# Printing4.net
KiCad netlist of a schematic drawn in Altium Designer
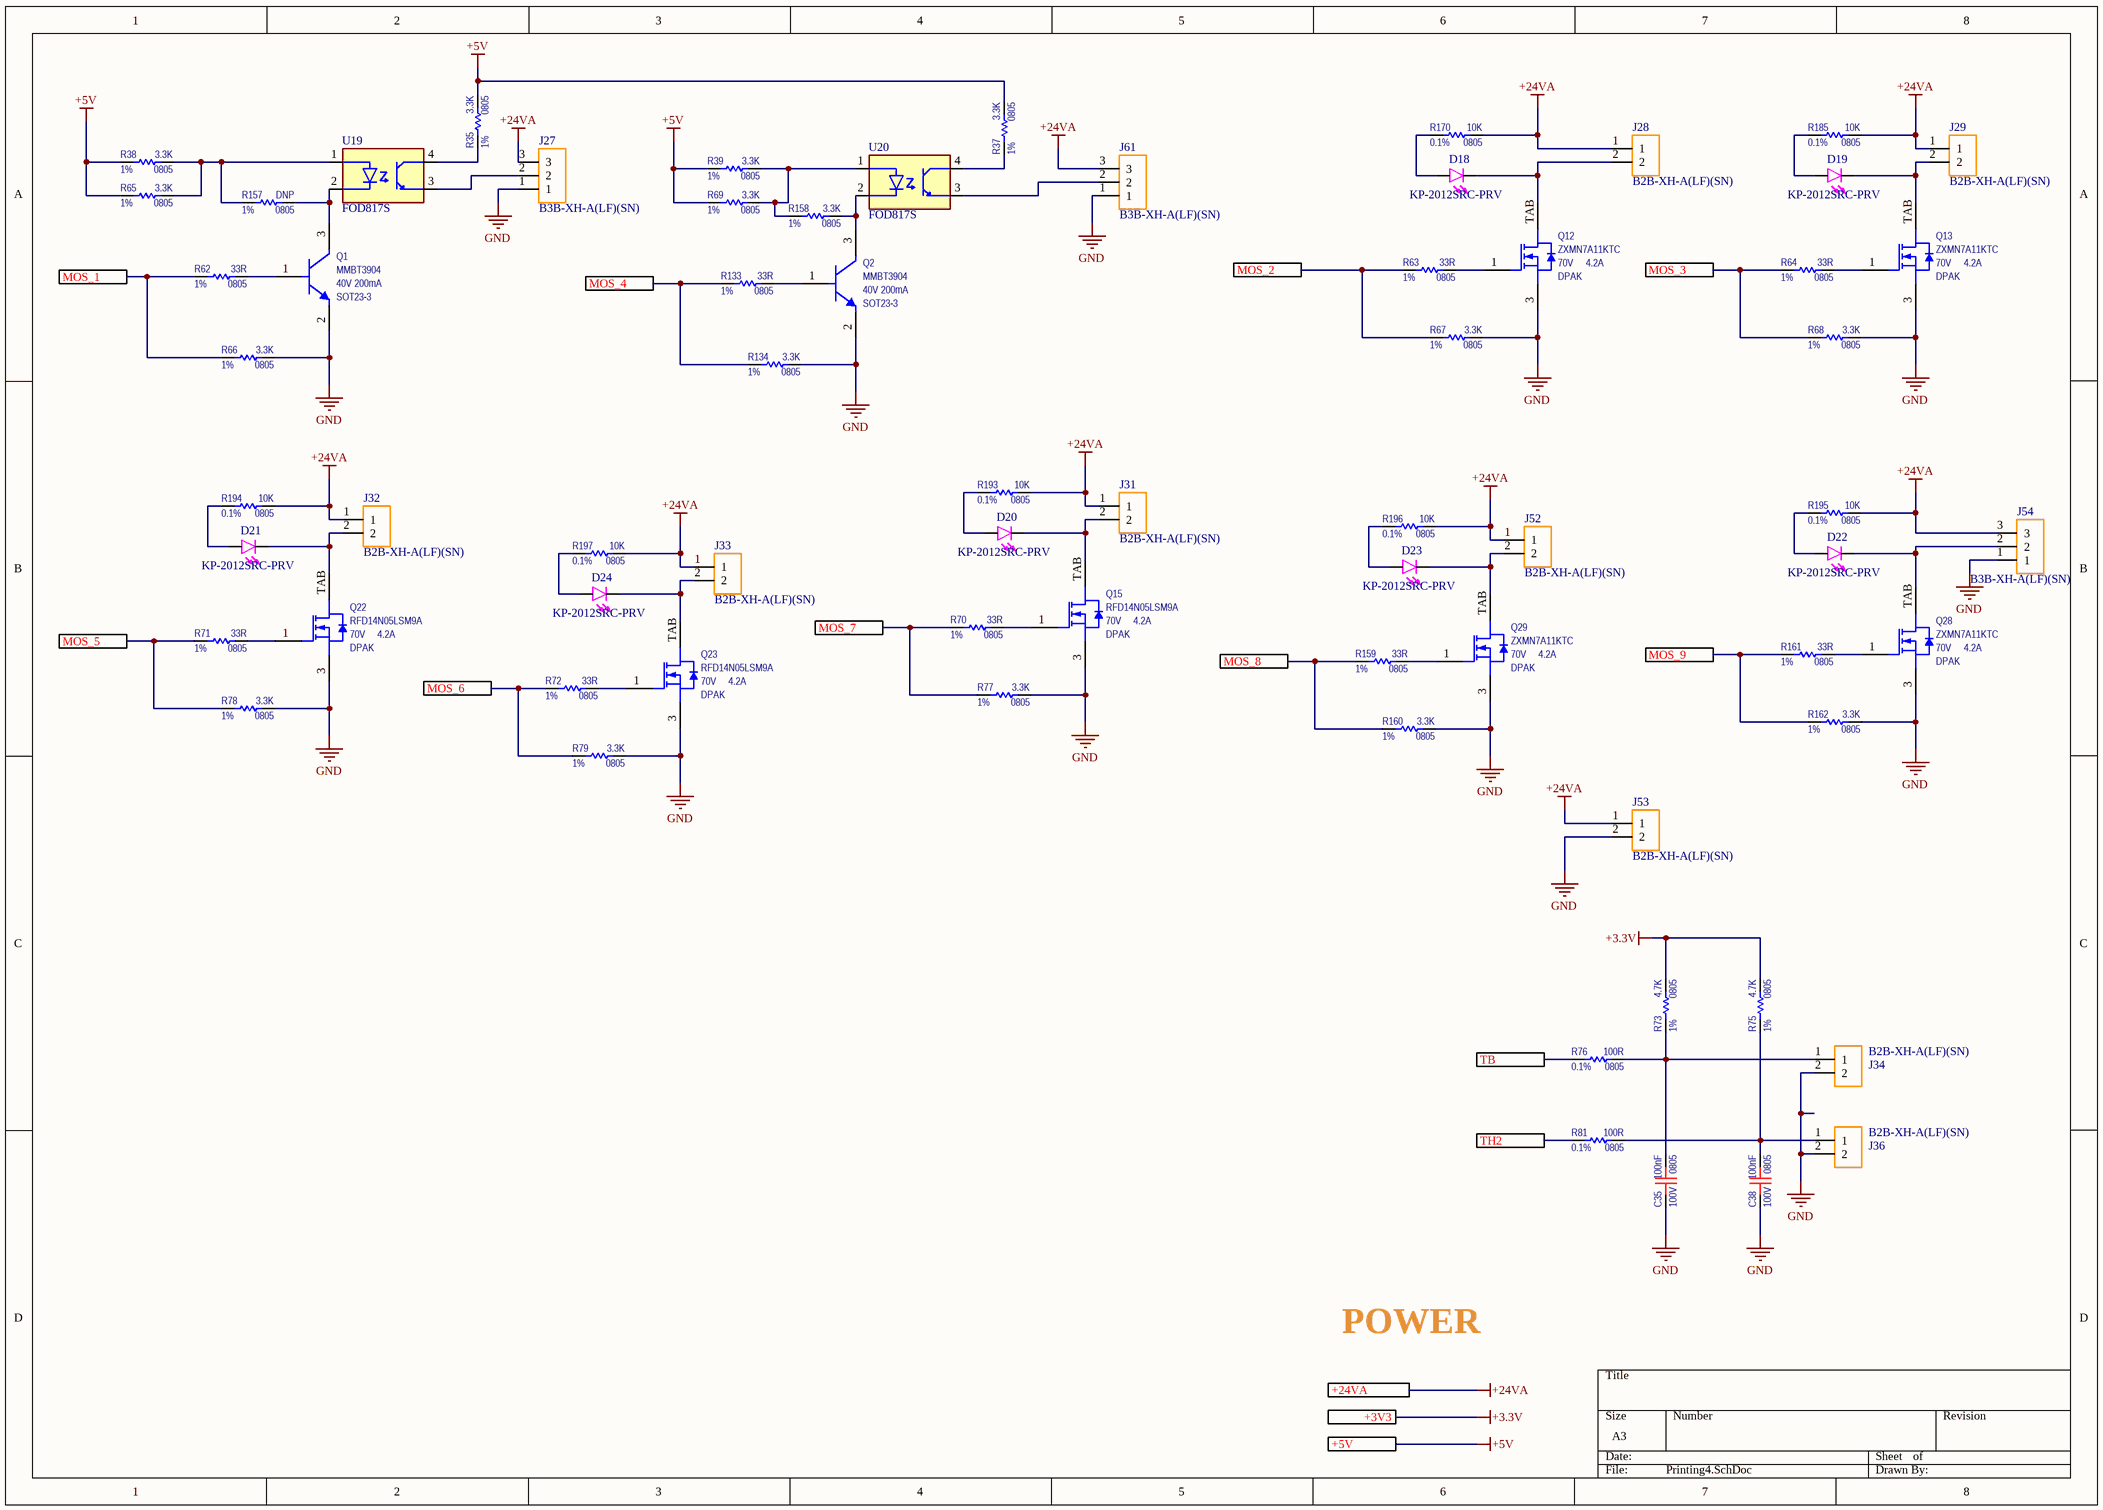
[diagram p0: Printing4.SchDoc]

(export (version "E")
  (design (tool "Eeschema 10.0.6"))
  (components
    (comp (ref "C35")
      (value "100nF")
      (footprint "C_0805_GEN_1.40H")
      (description "CAP_CER_100nF_100V_X7R_10%_0805")
      (fields
        (field (name "VOLTAGE") "100V")
        (field (name "PACKAGE") "0805")
        (field (name "SIMILAR PART") "C0805C104J1RECAUTO7210; C0805X104J1RECAUTO")
        (field (name "TOLERANCE") "10%")
        (field (name "ADDED BY") "İlhanT")
        (field (name "CHECKED BY") "İlkerU")
      )
      (libsource (lib "FireANTs_HwLibDB") (part "ESDSafeCapacitor"))
    )
    (comp (ref "C38")
      (value "100nF")
      (footprint "C_0805_GEN_1.40H")
      (description "CAP_CER_100nF_100V_X7R_10%_0805")
      (fields
        (field (name "VOLTAGE") "100V")
        (field (name "PACKAGE") "0805")
        (field (name "SIMILAR PART") "C0805C104J1RECAUTO7210; C0805X104J1RECAUTO")
        (field (name "TOLERANCE") "10%")
        (field (name "ADDED BY") "İlhanT")
        (field (name "CHECKED BY") "İlkerU")
      )
      (libsource (lib "FireANTs_HwLibDB") (part "ESDSafeCapacitor"))
    )
    (comp (ref "D18")
      (value "KP-2012SRC-PRV")
      (footprint "0805 LED")
      (description "KP-2012SRC-PRV Red LED, 640 nm 2012 (0805), Rectangle Lens SMD package")
      (fields (field (name "MANUFACTURER") "Kingbright"))
      (libsource (lib "Printing") (part "KP-2012SRC-PRV"))
    )
    (comp (ref "D19")
      (value "KP-2012SRC-PRV")
      (footprint "0805 LED")
      (description "KP-2012SRC-PRV Red LED, 640 nm 2012 (0805), Rectangle Lens SMD package")
      (fields (field (name "MANUFACTURER") "Kingbright"))
      (libsource (lib "Printing") (part "KP-2012SRC-PRV"))
    )
    (comp (ref "D20")
      (value "KP-2012SRC-PRV")
      (footprint "0805 LED")
      (description "KP-2012SRC-PRV Red LED, 640 nm 2012 (0805), Rectangle Lens SMD package")
      (fields (field (name "MANUFACTURER") "Kingbright"))
      (libsource (lib "Printing") (part "KP-2012SRC-PRV"))
    )
    (comp (ref "D21")
      (value "KP-2012SRC-PRV")
      (footprint "0805 LED")
      (description "KP-2012SRC-PRV Red LED, 640 nm 2012 (0805), Rectangle Lens SMD package")
      (fields (field (name "MANUFACTURER") "Kingbright"))
      (libsource (lib "Printing") (part "KP-2012SRC-PRV"))
    )
    (comp (ref "D22")
      (value "KP-2012SRC-PRV")
      (footprint "0805 LED")
      (description "KP-2012SRC-PRV Red LED, 640 nm 2012 (0805), Rectangle Lens SMD package")
      (fields (field (name "MANUFACTURER") "Kingbright"))
      (libsource (lib "Printing") (part "KP-2012SRC-PRV"))
    )
    (comp (ref "D23")
      (value "KP-2012SRC-PRV")
      (footprint "0805 LED")
      (description "KP-2012SRC-PRV Red LED, 640 nm 2012 (0805), Rectangle Lens SMD package")
      (fields (field (name "MANUFACTURER") "Kingbright"))
      (libsource (lib "Printing") (part "KP-2012SRC-PRV"))
    )
    (comp (ref "D24")
      (value "KP-2012SRC-PRV")
      (footprint "0805 LED")
      (description "KP-2012SRC-PRV Red LED, 640 nm 2012 (0805), Rectangle Lens SMD package")
      (fields (field (name "MANUFACTURER") "Kingbright"))
      (libsource (lib "Printing") (part "KP-2012SRC-PRV"))
    )
    (comp (ref "J27")
      (value "B3B-XH-A(LF)(SN)")
      (footprint "JST_B3B-XH-A(LF)(SN)")
      (libsource (lib "Printing") (part "B3B-XH-A(LF)(SN)"))
    )
    (comp (ref "J28")
      (value "B2B-XH-A(LF)(SN)")
      (footprint "JST_B2B-XH-A(LF)(SN)")
      (description "Connector Header Through Hole 2 position 0.098 (2.50mm)")
      (fields (field (name "MF") "JST Sales"))
      (libsource (lib "Printing") (part "B2B-XH-A(LF)(SN)"))
    )
    (comp (ref "J29")
      (value "B2B-XH-A(LF)(SN)")
      (footprint "JST_B2B-XH-A(LF)(SN)")
      (description "Connector Header Through Hole 2 position 0.098 (2.50mm)")
      (fields (field (name "MF") "JST Sales"))
      (libsource (lib "Printing") (part "B2B-XH-A(LF)(SN)"))
    )
    (comp (ref "J31")
      (value "B2B-XH-A(LF)(SN)")
      (footprint "JST_B2B-XH-A(LF)(SN)")
      (description "Connector Header Through Hole 2 position 0.098 (2.50mm)")
      (fields (field (name "MF") "JST Sales"))
      (libsource (lib "Printing") (part "B2B-XH-A(LF)(SN)"))
    )
    (comp (ref "J32")
      (value "B2B-XH-A(LF)(SN)")
      (footprint "JST_B2B-XH-A(LF)(SN)")
      (description "Connector Header Through Hole 2 position 0.098 (2.50mm)")
      (fields (field (name "MF") "JST Sales"))
      (libsource (lib "Printing") (part "B2B-XH-A(LF)(SN)"))
    )
    (comp (ref "J33")
      (value "B2B-XH-A(LF)(SN)")
      (footprint "JST_B2B-XH-A(LF)(SN)")
      (description "Connector Header Through Hole 2 position 0.098 (2.50mm)")
      (fields (field (name "MF") "JST Sales"))
      (libsource (lib "Printing") (part "B2B-XH-A(LF)(SN)"))
    )
    (comp (ref "J34")
      (value "B2B-XH-A(LF)(SN)")
      (footprint "JST_B2B-XH-A(LF)(SN)")
      (description "Connector Header Through Hole 2 position 0.098 (2.50mm)")
      (fields (field (name "MF") "JST Sales"))
      (libsource (lib "Printing") (part "B2B-XH-A(LF)(SN)"))
    )
    (comp (ref "J36")
      (value "B2B-XH-A(LF)(SN)")
      (footprint "JST_B2B-XH-A(LF)(SN)")
      (description "Connector Header Through Hole 2 position 0.098 (2.50mm)")
      (fields (field (name "MF") "JST Sales"))
      (libsource (lib "Printing") (part "B2B-XH-A(LF)(SN)"))
    )
    (comp (ref "J52")
      (value "B2B-XH-A(LF)(SN)")
      (footprint "JST_B2B-XH-A(LF)(SN)")
      (description "Connector Header Through Hole 2 position 0.098 (2.50mm)")
      (fields (field (name "MF") "JST Sales"))
      (libsource (lib "Printing") (part "B2B-XH-A(LF)(SN)"))
    )
    (comp (ref "J53")
      (value "B2B-XH-A(LF)(SN)")
      (footprint "JST_B2B-XH-A(LF)(SN)")
      (description "Connector Header Through Hole 2 position 0.098 (2.50mm)")
      (fields (field (name "MF") "JST Sales"))
      (libsource (lib "Printing") (part "B2B-XH-A(LF)(SN)"))
    )
    (comp (ref "J54")
      (value "B3B-XH-A(LF)(SN)")
      (footprint "JST_B3B-XH-A(LF)(SN)")
      (libsource (lib "Printing") (part "B3B-XH-A(LF)(SN)"))
    )
    (comp (ref "J61")
      (value "B3B-XH-A(LF)(SN)")
      (footprint "JST_B3B-XH-A(LF)(SN)")
      (libsource (lib "Printing") (part "B3B-XH-A(LF)(SN)"))
    )
    (comp (ref "Q1")
      (value "MMBT3904")
      (footprint "SOT23-3_MMBT3904,215")
      (description "TRA_NPN_SING_40V_200mA_VSAT300mV_SOT23-3")
      (fields
        (field (name "CURRENT") "200mA")
        (field (name "VOLTAGE") "40V")
        (field (name "PACKAGE") "SOT23-3")
        (field (name "SIMILAR PART") "SST3904HZGT116; PMBT3904,235")
        (field (name "TOLERANCE") "X")
        (field (name "ADDED BY") "HasanA")
        (field (name "CHECKED BY") "EserC")
      )
      (libsource (lib "FireANTs_HwLibDB") (part "SingleNPN_B1E2C3"))
    )
    (comp (ref "Q2")
      (value "MMBT3904")
      (footprint "SOT23-3_MMBT3904,215")
      (description "TRA_NPN_SING_40V_200mA_VSAT300mV_SOT23-3")
      (fields
        (field (name "CURRENT") "200mA")
        (field (name "VOLTAGE") "40V")
        (field (name "PACKAGE") "SOT23-3")
        (field (name "SIMILAR PART") "SST3904HZGT116; PMBT3904,235")
        (field (name "TOLERANCE") "X")
        (field (name "ADDED BY") "HasanA")
        (field (name "CHECKED BY") "EserC")
      )
      (libsource (lib "FireANTs_HwLibDB") (part "SingleNPN_B1E2C3"))
    )
    (comp (ref "Q12")
      (value "ZXMN7A11KTC")
      (footprint "DPAK_SQD50N10-8M9L")
      (description "TRA_NMOS_SING_100V_50A_TH2V_DPAK")
      (fields
        (field (name "CURRENT") "4.2A")
        (field (name "VOLTAGE") "70V")
        (field (name "PACKAGE") "DPAK")
        (field (name "SIMILAR PART") "SQM70060EL_GE3; SQM100N10-10_GE3")
        (field (name "TOLERANCE") "X")
        (field (name "ADDED BY") "İlhanT")
        (field (name "CHECKED BY") "YasinY")
      )
      (libsource (lib "FireANTs_HwLibDB") (part "SingleNMOS_G1S3DTAB"))
    )
    (comp (ref "Q13")
      (value "ZXMN7A11KTC")
      (footprint "DPAK_SQD50N10-8M9L")
      (description "TRA_NMOS_SING_100V_50A_TH2V_DPAK")
      (fields
        (field (name "CURRENT") "4.2A")
        (field (name "VOLTAGE") "70V")
        (field (name "PACKAGE") "DPAK")
        (field (name "SIMILAR PART") "SQM70060EL_GE3; SQM100N10-10_GE3")
        (field (name "TOLERANCE") "X")
        (field (name "ADDED BY") "İlhanT")
        (field (name "CHECKED BY") "YasinY")
      )
      (libsource (lib "FireANTs_HwLibDB") (part "SingleNMOS_G1S3DTAB"))
    )
    (comp (ref "Q15")
      (value "RFD14N05LSM9A")
      (footprint "DPAK_SQD50N10-8M9L")
      (description "TRA_NMOS_SING_100V_50A_TH2V_DPAK")
      (fields
        (field (name "CURRENT") "4.2A")
        (field (name "VOLTAGE") "70V")
        (field (name "PACKAGE") "DPAK")
        (field (name "SIMILAR PART") "SQM70060EL_GE3; SQM100N10-10_GE3")
        (field (name "TOLERANCE") "X")
        (field (name "ADDED BY") "İlhanT")
        (field (name "CHECKED BY") "YasinY")
      )
      (libsource (lib "FireANTs_HwLibDB") (part "SingleNMOS_G1S3DTAB"))
    )
    (comp (ref "Q22")
      (value "RFD14N05LSM9A")
      (footprint "DPAK_SQD50N10-8M9L")
      (description "TRA_NMOS_SING_100V_50A_TH2V_DPAK")
      (fields
        (field (name "CURRENT") "4.2A")
        (field (name "VOLTAGE") "70V")
        (field (name "PACKAGE") "DPAK")
        (field (name "SIMILAR PART") "SQM70060EL_GE3; SQM100N10-10_GE3")
        (field (name "TOLERANCE") "X")
        (field (name "ADDED BY") "İlhanT")
        (field (name "CHECKED BY") "YasinY")
      )
      (libsource (lib "FireANTs_HwLibDB") (part "SingleNMOS_G1S3DTAB"))
    )
    (comp (ref "Q23")
      (value "RFD14N05LSM9A")
      (footprint "DPAK_SQD50N10-8M9L")
      (description "TRA_NMOS_SING_100V_50A_TH2V_DPAK")
      (fields
        (field (name "CURRENT") "4.2A")
        (field (name "VOLTAGE") "70V")
        (field (name "PACKAGE") "DPAK")
        (field (name "SIMILAR PART") "SQM70060EL_GE3; SQM100N10-10_GE3")
        (field (name "TOLERANCE") "X")
        (field (name "ADDED BY") "İlhanT")
        (field (name "CHECKED BY") "YasinY")
      )
      (libsource (lib "FireANTs_HwLibDB") (part "SingleNMOS_G1S3DTAB"))
    )
    (comp (ref "Q28")
      (value "ZXMN7A11KTC")
      (footprint "DPAK_SQD50N10-8M9L")
      (description "TRA_NMOS_SING_100V_50A_TH2V_DPAK")
      (fields
        (field (name "CURRENT") "4.2A")
        (field (name "VOLTAGE") "70V")
        (field (name "PACKAGE") "DPAK")
        (field (name "SIMILAR PART") "SQM70060EL_GE3; SQM100N10-10_GE3")
        (field (name "TOLERANCE") "X")
        (field (name "ADDED BY") "İlhanT")
        (field (name "CHECKED BY") "YasinY")
      )
      (libsource (lib "FireANTs_HwLibDB") (part "SingleNMOS_G1S3DTAB"))
    )
    (comp (ref "Q29")
      (value "ZXMN7A11KTC")
      (footprint "DPAK_SQD50N10-8M9L")
      (description "TRA_NMOS_SING_100V_50A_TH2V_DPAK")
      (fields
        (field (name "CURRENT") "4.2A")
        (field (name "VOLTAGE") "70V")
        (field (name "PACKAGE") "DPAK")
        (field (name "SIMILAR PART") "SQM70060EL_GE3; SQM100N10-10_GE3")
        (field (name "TOLERANCE") "X")
        (field (name "ADDED BY") "İlhanT")
        (field (name "CHECKED BY") "YasinY")
      )
      (libsource (lib "FireANTs_HwLibDB") (part "SingleNMOS_G1S3DTAB"))
    )
    (comp (ref "R35")
      (value "3.3K")
      (footprint "R_0805_GEN_0.70H")
      (description "RES_STD_3.3K_0.125W_1%_100ppm_0805")
      (fields
        (field (name "TOLERANCE") "1%")
        (field (name "PACKAGE") "0805")
        (field (name "VOLTAGE") "150V")
        (field (name "Comment") "StandardResistor")
        (field (name "ADDED BY") "HasanA")
        (field (name "CHECKED BY") "YasinY")
      )
      (libsource (lib "FireANTs_HwLibDB") (part "StandardResistor"))
    )
    (comp (ref "R37")
      (value "3.3K")
      (footprint "R_0805_GEN_0.70H")
      (description "RES_STD_3.3K_0.125W_1%_100ppm_0805")
      (fields
        (field (name "TOLERANCE") "1%")
        (field (name "PACKAGE") "0805")
        (field (name "VOLTAGE") "150V")
        (field (name "Comment") "StandardResistor")
        (field (name "ADDED BY") "HasanA")
        (field (name "CHECKED BY") "YasinY")
      )
      (libsource (lib "FireANTs_HwLibDB") (part "StandardResistor"))
    )
    (comp (ref "R38")
      (value "3.3K")
      (footprint "R_0805_GEN_0.70H")
      (description "RES_STD_3.3K_0.125W_1%_100ppm_0805")
      (fields
        (field (name "TOLERANCE") "1%")
        (field (name "PACKAGE") "0805")
        (field (name "VOLTAGE") "150V")
        (field (name "Comment") "StandardResistor")
        (field (name "ADDED BY") "HasanA")
        (field (name "CHECKED BY") "YasinY")
      )
      (libsource (lib "FireANTs_HwLibDB") (part "StandardResistor"))
    )
    (comp (ref "R39")
      (value "3.3K")
      (footprint "R_0805_GEN_0.70H")
      (description "RES_STD_3.3K_0.125W_1%_100ppm_0805")
      (fields
        (field (name "TOLERANCE") "1%")
        (field (name "PACKAGE") "0805")
        (field (name "VOLTAGE") "150V")
        (field (name "Comment") "StandardResistor")
        (field (name "ADDED BY") "HasanA")
        (field (name "CHECKED BY") "YasinY")
      )
      (libsource (lib "FireANTs_HwLibDB") (part "StandardResistor"))
    )
    (comp (ref "R62")
      (value "33R")
      (footprint "R_0805_GEN_0.70H")
      (description "RES_STD_33R_0.125W_1%_100ppm_0805")
      (fields
        (field (name "TOLERANCE") "1%")
        (field (name "PACKAGE") "0805")
        (field (name "VOLTAGE") "150V")
        (field (name "Comment") "StandardResistor")
        (field (name "ADDED BY") "HasanA")
        (field (name "CHECKED BY") "YasinY")
      )
      (libsource (lib "FireANTs_HwLibDB") (part "StandardResistor"))
    )
    (comp (ref "R63")
      (value "33R")
      (footprint "R_0805_GEN_0.70H")
      (description "RES_STD_33R_0.125W_1%_100ppm_0805")
      (fields
        (field (name "TOLERANCE") "1%")
        (field (name "PACKAGE") "0805")
        (field (name "VOLTAGE") "150V")
        (field (name "Comment") "StandardResistor")
        (field (name "ADDED BY") "HasanA")
        (field (name "CHECKED BY") "YasinY")
      )
      (libsource (lib "FireANTs_HwLibDB") (part "StandardResistor"))
    )
    (comp (ref "R64")
      (value "33R")
      (footprint "R_0805_GEN_0.70H")
      (description "RES_STD_33R_0.125W_1%_100ppm_0805")
      (fields
        (field (name "TOLERANCE") "1%")
        (field (name "PACKAGE") "0805")
        (field (name "VOLTAGE") "150V")
        (field (name "Comment") "StandardResistor")
        (field (name "ADDED BY") "HasanA")
        (field (name "CHECKED BY") "YasinY")
      )
      (libsource (lib "FireANTs_HwLibDB") (part "StandardResistor"))
    )
    (comp (ref "R65")
      (value "3.3K")
      (footprint "R_0805_GEN_0.70H")
      (description "RES_STD_3.3K_0.125W_1%_100ppm_0805")
      (fields
        (field (name "TOLERANCE") "1%")
        (field (name "PACKAGE") "0805")
        (field (name "VOLTAGE") "150V")
        (field (name "Comment") "StandardResistor")
        (field (name "ADDED BY") "HasanA")
        (field (name "CHECKED BY") "YasinY")
      )
      (libsource (lib "FireANTs_HwLibDB") (part "StandardResistor"))
    )
    (comp (ref "R66")
      (value "3.3K")
      (footprint "R_0805_GEN_0.70H")
      (description "RES_STD_3.3K_0.125W_1%_100ppm_0805")
      (fields
        (field (name "TOLERANCE") "1%")
        (field (name "PACKAGE") "0805")
        (field (name "VOLTAGE") "150V")
        (field (name "Comment") "StandardResistor")
        (field (name "ADDED BY") "HasanA")
        (field (name "CHECKED BY") "YasinY")
      )
      (libsource (lib "FireANTs_HwLibDB") (part "StandardResistor"))
    )
    (comp (ref "R67")
      (value "3.3K")
      (footprint "R_0805_GEN_0.70H")
      (description "RES_STD_3.3K_0.125W_1%_100ppm_0805")
      (fields
        (field (name "TOLERANCE") "1%")
        (field (name "PACKAGE") "0805")
        (field (name "VOLTAGE") "150V")
        (field (name "Comment") "StandardResistor")
        (field (name "ADDED BY") "HasanA")
        (field (name "CHECKED BY") "YasinY")
      )
      (libsource (lib "FireANTs_HwLibDB") (part "StandardResistor"))
    )
    (comp (ref "R68")
      (value "3.3K")
      (footprint "R_0805_GEN_0.70H")
      (description "RES_STD_3.3K_0.125W_1%_100ppm_0805")
      (fields
        (field (name "TOLERANCE") "1%")
        (field (name "PACKAGE") "0805")
        (field (name "VOLTAGE") "150V")
        (field (name "Comment") "StandardResistor")
        (field (name "ADDED BY") "HasanA")
        (field (name "CHECKED BY") "YasinY")
      )
      (libsource (lib "FireANTs_HwLibDB") (part "StandardResistor"))
    )
    (comp (ref "R69")
      (value "3.3K")
      (footprint "R_0805_GEN_0.70H")
      (description "RES_STD_3.3K_0.125W_1%_100ppm_0805")
      (fields
        (field (name "TOLERANCE") "1%")
        (field (name "PACKAGE") "0805")
        (field (name "VOLTAGE") "150V")
        (field (name "Comment") "StandardResistor")
        (field (name "ADDED BY") "HasanA")
        (field (name "CHECKED BY") "YasinY")
      )
      (libsource (lib "FireANTs_HwLibDB") (part "StandardResistor"))
    )
    (comp (ref "R70")
      (value "33R")
      (footprint "R_0805_GEN_0.70H")
      (description "RES_STD_33R_0.125W_1%_100ppm_0805")
      (fields
        (field (name "TOLERANCE") "1%")
        (field (name "PACKAGE") "0805")
        (field (name "VOLTAGE") "150V")
        (field (name "Comment") "StandardResistor")
        (field (name "ADDED BY") "HasanA")
        (field (name "CHECKED BY") "YasinY")
      )
      (libsource (lib "FireANTs_HwLibDB") (part "StandardResistor"))
    )
    (comp (ref "R71")
      (value "33R")
      (footprint "R_0805_GEN_0.70H")
      (description "RES_STD_33R_0.125W_1%_100ppm_0805")
      (fields
        (field (name "TOLERANCE") "1%")
        (field (name "PACKAGE") "0805")
        (field (name "VOLTAGE") "150V")
        (field (name "Comment") "StandardResistor")
        (field (name "ADDED BY") "HasanA")
        (field (name "CHECKED BY") "YasinY")
      )
      (libsource (lib "FireANTs_HwLibDB") (part "StandardResistor"))
    )
    (comp (ref "R72")
      (value "33R")
      (footprint "R_0805_GEN_0.70H")
      (description "RES_STD_33R_0.125W_1%_100ppm_0805")
      (fields
        (field (name "TOLERANCE") "1%")
        (field (name "PACKAGE") "0805")
        (field (name "VOLTAGE") "150V")
        (field (name "Comment") "StandardResistor")
        (field (name "ADDED BY") "HasanA")
        (field (name "CHECKED BY") "YasinY")
      )
      (libsource (lib "FireANTs_HwLibDB") (part "StandardResistor"))
    )
    (comp (ref "R73")
      (value "4.7K")
      (footprint "R_0805_GEN_0.60H")
      (description "RES_STD_4.7K_0.125W_1%_100ppm_0805")
      (fields
        (field (name "TOLERANCE") "1%")
        (field (name "PACKAGE") "0805")
        (field (name "VOLTAGE") "150V")
        (field (name "Comment") "StandardResistor")
        (field (name "ADDED BY") "SonerI")
        (field (name "CHECKED BY") "YasinY")
      )
      (libsource (lib "FireANTs_HwLibDB") (part "StandardResistor"))
    )
    (comp (ref "R75")
      (value "4.7K")
      (footprint "R_0805_GEN_0.60H")
      (description "RES_STD_4.7K_0.125W_1%_100ppm_0805")
      (fields
        (field (name "TOLERANCE") "1%")
        (field (name "PACKAGE") "0805")
        (field (name "VOLTAGE") "150V")
        (field (name "Comment") "StandardResistor")
        (field (name "ADDED BY") "SonerI")
        (field (name "CHECKED BY") "YasinY")
      )
      (libsource (lib "FireANTs_HwLibDB") (part "StandardResistor"))
    )
    (comp (ref "R76")
      (value "100R")
      (footprint "R_0805_GEN_0.70H")
      (description "RES_STD_100R_0.125W_0.1%_10ppm_0805")
      (fields
        (field (name "TOLERANCE") "0.1%")
        (field (name "PACKAGE") "0805")
        (field (name "SIMILAR PART") "RNCF0805TKY100R; RG2012N-101-W-T1")
        (field (name "VOLTAGE") "150V")
        (field (name "ADDED BY") "HasanA")
        (field (name "CHECKED BY") "YasinY")
      )
      (libsource (lib "FireANTs_HwLibDB") (part "StandardResistor"))
    )
    (comp (ref "R77")
      (value "3.3K")
      (footprint "R_0805_GEN_0.70H")
      (description "RES_STD_3.3K_0.125W_1%_100ppm_0805")
      (fields
        (field (name "TOLERANCE") "1%")
        (field (name "PACKAGE") "0805")
        (field (name "VOLTAGE") "150V")
        (field (name "Comment") "StandardResistor")
        (field (name "ADDED BY") "HasanA")
        (field (name "CHECKED BY") "YasinY")
      )
      (libsource (lib "FireANTs_HwLibDB") (part "StandardResistor"))
    )
    (comp (ref "R78")
      (value "3.3K")
      (footprint "R_0805_GEN_0.70H")
      (description "RES_STD_3.3K_0.125W_1%_100ppm_0805")
      (fields
        (field (name "TOLERANCE") "1%")
        (field (name "PACKAGE") "0805")
        (field (name "VOLTAGE") "150V")
        (field (name "Comment") "StandardResistor")
        (field (name "ADDED BY") "HasanA")
        (field (name "CHECKED BY") "YasinY")
      )
      (libsource (lib "FireANTs_HwLibDB") (part "StandardResistor"))
    )
    (comp (ref "R79")
      (value "3.3K")
      (footprint "R_0805_GEN_0.70H")
      (description "RES_STD_3.3K_0.125W_1%_100ppm_0805")
      (fields
        (field (name "TOLERANCE") "1%")
        (field (name "PACKAGE") "0805")
        (field (name "VOLTAGE") "150V")
        (field (name "Comment") "StandardResistor")
        (field (name "ADDED BY") "HasanA")
        (field (name "CHECKED BY") "YasinY")
      )
      (libsource (lib "FireANTs_HwLibDB") (part "StandardResistor"))
    )
    (comp (ref "R81")
      (value "100R")
      (footprint "R_0805_GEN_0.70H")
      (description "RES_STD_100R_0.125W_0.1%_10ppm_0805")
      (fields
        (field (name "TOLERANCE") "0.1%")
        (field (name "PACKAGE") "0805")
        (field (name "SIMILAR PART") "RNCF0805TKY100R; RG2012N-101-W-T1")
        (field (name "VOLTAGE") "150V")
        (field (name "ADDED BY") "HasanA")
        (field (name "CHECKED BY") "YasinY")
      )
      (libsource (lib "FireANTs_HwLibDB") (part "StandardResistor"))
    )
    (comp (ref "R133")
      (value "33R")
      (footprint "R_0805_GEN_0.70H")
      (description "RES_STD_33R_0.125W_1%_100ppm_0805")
      (fields
        (field (name "TOLERANCE") "1%")
        (field (name "PACKAGE") "0805")
        (field (name "VOLTAGE") "150V")
        (field (name "Comment") "StandardResistor")
        (field (name "ADDED BY") "HasanA")
        (field (name "CHECKED BY") "YasinY")
      )
      (libsource (lib "FireANTs_HwLibDB") (part "StandardResistor"))
    )
    (comp (ref "R134")
      (value "3.3K")
      (footprint "R_0805_GEN_0.70H")
      (description "RES_STD_3.3K_0.125W_1%_100ppm_0805")
      (fields
        (field (name "TOLERANCE") "1%")
        (field (name "PACKAGE") "0805")
        (field (name "VOLTAGE") "150V")
        (field (name "Comment") "StandardResistor")
        (field (name "ADDED BY") "HasanA")
        (field (name "CHECKED BY") "YasinY")
      )
      (libsource (lib "FireANTs_HwLibDB") (part "StandardResistor"))
    )
    (comp (ref "R157")
      (value "DNP")
      (footprint "R_0805_GEN_0.70H")
      (description "RES_STD_3.3K_0.125W_1%_100ppm_0805")
      (fields
        (field (name "TOLERANCE") "1%")
        (field (name "PACKAGE") "0805")
        (field (name "VOLTAGE") "150V")
        (field (name "Comment") "StandardResistor")
        (field (name "ADDED BY") "HasanA")
        (field (name "CHECKED BY") "YasinY")
      )
      (libsource (lib "FireANTs_HwLibDB") (part "StandardResistor"))
    )
    (comp (ref "R158")
      (value "3.3K")
      (footprint "R_0805_GEN_0.70H")
      (description "RES_STD_3.3K_0.125W_1%_100ppm_0805")
      (fields
        (field (name "TOLERANCE") "1%")
        (field (name "PACKAGE") "0805")
        (field (name "VOLTAGE") "150V")
        (field (name "Comment") "StandardResistor")
        (field (name "ADDED BY") "HasanA")
        (field (name "CHECKED BY") "YasinY")
      )
      (libsource (lib "FireANTs_HwLibDB") (part "StandardResistor"))
    )
    (comp (ref "R159")
      (value "33R")
      (footprint "R_0805_GEN_0.70H")
      (description "RES_STD_33R_0.125W_1%_100ppm_0805")
      (fields
        (field (name "TOLERANCE") "1%")
        (field (name "PACKAGE") "0805")
        (field (name "VOLTAGE") "150V")
        (field (name "Comment") "StandardResistor")
        (field (name "ADDED BY") "HasanA")
        (field (name "CHECKED BY") "YasinY")
      )
      (libsource (lib "FireANTs_HwLibDB") (part "StandardResistor"))
    )
    (comp (ref "R160")
      (value "3.3K")
      (footprint "R_0805_GEN_0.70H")
      (description "RES_STD_3.3K_0.125W_1%_100ppm_0805")
      (fields
        (field (name "TOLERANCE") "1%")
        (field (name "PACKAGE") "0805")
        (field (name "VOLTAGE") "150V")
        (field (name "Comment") "StandardResistor")
        (field (name "ADDED BY") "HasanA")
        (field (name "CHECKED BY") "YasinY")
      )
      (libsource (lib "FireANTs_HwLibDB") (part "StandardResistor"))
    )
    (comp (ref "R161")
      (value "33R")
      (footprint "R_0805_GEN_0.70H")
      (description "RES_STD_33R_0.125W_1%_100ppm_0805")
      (fields
        (field (name "TOLERANCE") "1%")
        (field (name "PACKAGE") "0805")
        (field (name "VOLTAGE") "150V")
        (field (name "Comment") "StandardResistor")
        (field (name "ADDED BY") "HasanA")
        (field (name "CHECKED BY") "YasinY")
      )
      (libsource (lib "FireANTs_HwLibDB") (part "StandardResistor"))
    )
    (comp (ref "R162")
      (value "3.3K")
      (footprint "R_0805_GEN_0.70H")
      (description "RES_STD_3.3K_0.125W_1%_100ppm_0805")
      (fields
        (field (name "TOLERANCE") "1%")
        (field (name "PACKAGE") "0805")
        (field (name "VOLTAGE") "150V")
        (field (name "Comment") "StandardResistor")
        (field (name "ADDED BY") "HasanA")
        (field (name "CHECKED BY") "YasinY")
      )
      (libsource (lib "FireANTs_HwLibDB") (part "StandardResistor"))
    )
    (comp (ref "R170")
      (value "10K")
      (footprint "R_0805_GEN_0.70H")
      (description "RES_STD_2K_0.125W_0.1%_25ppm_0805")
      (fields
        (field (name "TOLERANCE") "0.1%")
        (field (name "PACKAGE") "0805")
        (field (name "SIMILAR PART") "ERA-6ARB202V")
        (field (name "VOLTAGE") "100V")
        (field (name "ADDED BY") "İlhanT")
        (field (name "CHECKED BY") "YasinY")
      )
      (libsource (lib "FireANTs_HwLibDB") (part "StandardResistor"))
    )
    (comp (ref "R185")
      (value "10K")
      (footprint "R_0805_GEN_0.70H")
      (description "RES_STD_2K_0.125W_0.1%_25ppm_0805")
      (fields
        (field (name "TOLERANCE") "0.1%")
        (field (name "PACKAGE") "0805")
        (field (name "SIMILAR PART") "ERA-6ARB202V")
        (field (name "VOLTAGE") "100V")
        (field (name "ADDED BY") "İlhanT")
        (field (name "CHECKED BY") "YasinY")
      )
      (libsource (lib "FireANTs_HwLibDB") (part "StandardResistor"))
    )
    (comp (ref "R193")
      (value "10K")
      (footprint "R_0805_GEN_0.70H")
      (description "RES_STD_2K_0.125W_0.1%_25ppm_0805")
      (fields
        (field (name "TOLERANCE") "0.1%")
        (field (name "PACKAGE") "0805")
        (field (name "SIMILAR PART") "ERA-6ARB202V")
        (field (name "VOLTAGE") "100V")
        (field (name "ADDED BY") "İlhanT")
        (field (name "CHECKED BY") "YasinY")
      )
      (libsource (lib "FireANTs_HwLibDB") (part "StandardResistor"))
    )
    (comp (ref "R194")
      (value "10K")
      (footprint "R_0805_GEN_0.70H")
      (description "RES_STD_2K_0.125W_0.1%_25ppm_0805")
      (fields
        (field (name "TOLERANCE") "0.1%")
        (field (name "PACKAGE") "0805")
        (field (name "SIMILAR PART") "ERA-6ARB202V")
        (field (name "VOLTAGE") "100V")
        (field (name "ADDED BY") "İlhanT")
        (field (name "CHECKED BY") "YasinY")
      )
      (libsource (lib "FireANTs_HwLibDB") (part "StandardResistor"))
    )
    (comp (ref "R195")
      (value "10K")
      (footprint "R_0805_GEN_0.70H")
      (description "RES_STD_2K_0.125W_0.1%_25ppm_0805")
      (fields
        (field (name "TOLERANCE") "0.1%")
        (field (name "PACKAGE") "0805")
        (field (name "SIMILAR PART") "ERA-6ARB202V")
        (field (name "VOLTAGE") "100V")
        (field (name "ADDED BY") "İlhanT")
        (field (name "CHECKED BY") "YasinY")
      )
      (libsource (lib "FireANTs_HwLibDB") (part "StandardResistor"))
    )
    (comp (ref "R196")
      (value "10K")
      (footprint "R_0805_GEN_0.70H")
      (description "RES_STD_2K_0.125W_0.1%_25ppm_0805")
      (fields
        (field (name "TOLERANCE") "0.1%")
        (field (name "PACKAGE") "0805")
        (field (name "SIMILAR PART") "ERA-6ARB202V")
        (field (name "VOLTAGE") "100V")
        (field (name "ADDED BY") "İlhanT")
        (field (name "CHECKED BY") "YasinY")
      )
      (libsource (lib "FireANTs_HwLibDB") (part "StandardResistor"))
    )
    (comp (ref "R197")
      (value "10K")
      (footprint "R_0805_GEN_0.70H")
      (description "RES_STD_2K_0.125W_0.1%_25ppm_0805")
      (fields
        (field (name "TOLERANCE") "0.1%")
        (field (name "PACKAGE") "0805")
        (field (name "SIMILAR PART") "ERA-6ARB202V")
        (field (name "VOLTAGE") "100V")
        (field (name "ADDED BY") "İlhanT")
        (field (name "CHECKED BY") "YasinY")
      )
      (libsource (lib "FireANTs_HwLibDB") (part "StandardResistor"))
    )
    (comp (ref "U19")
      (value "FOD817S")
      (footprint "SOIC254P1016X385-4N")
      (description "Optoisolator Transistor Output 5000Vrms 1 Channel 4-SMD")
      (fields (field (name "MF") "ON Semiconductor"))
      (libsource (lib "Printing") (part "FOD817S"))
    )
    (comp (ref "U20")
      (value "FOD817S")
      (footprint "SOIC254P1016X385-4N")
      (description "Optoisolator Transistor Output 5000Vrms 1 Channel 4-SMD")
      (fields (field (name "MF") "ON Semiconductor"))
      (libsource (lib "Printing") (part "FOD817S"))
    )
  )
  (nets
    (net (code "1") (name "+3.3V") (class "Default")
      (node (ref "R73") (pin "2") (pinfunction "2_2") (pintype "passive"))
      (node (ref "R75") (pin "2") (pinfunction "2_2") (pintype "passive"))
    )
    (net (code "2") (name "+5V") (class "Default")
      (node (ref "R35") (pin "2") (pinfunction "2_2") (pintype "passive"))
      (node (ref "R37") (pin "2") (pinfunction "2_2") (pintype "passive"))
      (node (ref "R38") (pin "1") (pinfunction "1_1") (pintype "passive"))
      (node (ref "R39") (pin "1") (pinfunction "1_1") (pintype "passive"))
      (node (ref "R65") (pin "1") (pinfunction "1_1") (pintype "passive"))
      (node (ref "R69") (pin "1") (pinfunction "1_1") (pintype "passive"))
    )
    (net (code "3") (name "+24VA") (class "Default")
      (node (ref "J27") (pin "3") (pinfunction "3_3") (pintype "passive"))
      (node (ref "J28") (pin "1") (pinfunction "1_1") (pintype "passive"))
      (node (ref "J29") (pin "1") (pinfunction "1_1") (pintype "passive"))
      (node (ref "J31") (pin "1") (pinfunction "1_1") (pintype "passive"))
      (node (ref "J32") (pin "1") (pinfunction "1_1") (pintype "passive"))
      (node (ref "J33") (pin "1") (pinfunction "1_1") (pintype "passive"))
      (node (ref "J52") (pin "1") (pinfunction "1_1") (pintype "passive"))
      (node (ref "J53") (pin "1") (pinfunction "1_1") (pintype "passive"))
      (node (ref "J54") (pin "3") (pinfunction "3_3") (pintype "passive"))
      (node (ref "J61") (pin "3") (pinfunction "3_3") (pintype "passive"))
      (node (ref "R170") (pin "2") (pinfunction "2_2") (pintype "passive"))
      (node (ref "R185") (pin "2") (pinfunction "2_2") (pintype "passive"))
      (node (ref "R193") (pin "2") (pinfunction "2_2") (pintype "passive"))
      (node (ref "R194") (pin "2") (pinfunction "2_2") (pintype "passive"))
      (node (ref "R195") (pin "2") (pinfunction "2_2") (pintype "passive"))
      (node (ref "R196") (pin "2") (pinfunction "2_2") (pintype "passive"))
      (node (ref "R197") (pin "2") (pinfunction "2_2") (pintype "passive"))
    )
    (net (code "4") (name "/MOS_1") (class "Default")
      (node (ref "R62") (pin "1") (pinfunction "1_1") (pintype "passive"))
      (node (ref "R66") (pin "1") (pinfunction "1_1") (pintype "passive"))
    )
    (net (code "5") (name "/MOS_2") (class "Default")
      (node (ref "R63") (pin "1") (pinfunction "1_1") (pintype "passive"))
      (node (ref "R67") (pin "1") (pinfunction "1_1") (pintype "passive"))
    )
    (net (code "6") (name "/MOS_3") (class "Default")
      (node (ref "R64") (pin "1") (pinfunction "1_1") (pintype "passive"))
      (node (ref "R68") (pin "1") (pinfunction "1_1") (pintype "passive"))
    )
    (net (code "7") (name "/MOS_4") (class "Default")
      (node (ref "R133") (pin "1") (pinfunction "1_1") (pintype "passive"))
      (node (ref "R134") (pin "1") (pinfunction "1_1") (pintype "passive"))
    )
    (net (code "8") (name "/MOS_5") (class "Default")
      (node (ref "R71") (pin "1") (pinfunction "1_1") (pintype "passive"))
      (node (ref "R78") (pin "1") (pinfunction "1_1") (pintype "passive"))
    )
    (net (code "9") (name "/MOS_6") (class "Default")
      (node (ref "R72") (pin "1") (pinfunction "1_1") (pintype "passive"))
      (node (ref "R79") (pin "1") (pinfunction "1_1") (pintype "passive"))
    )
    (net (code "10") (name "/MOS_7") (class "Default")
      (node (ref "R70") (pin "1") (pinfunction "1_1") (pintype "passive"))
      (node (ref "R77") (pin "1") (pinfunction "1_1") (pintype "passive"))
    )
    (net (code "11") (name "/MOS_8") (class "Default")
      (node (ref "R159") (pin "1") (pinfunction "1_1") (pintype "passive"))
      (node (ref "R160") (pin "1") (pinfunction "1_1") (pintype "passive"))
    )
    (net (code "12") (name "/MOS_9") (class "Default")
      (node (ref "R161") (pin "1") (pinfunction "1_1") (pintype "passive"))
      (node (ref "R162") (pin "1") (pinfunction "1_1") (pintype "passive"))
    )
    (net (code "13") (name "/TB") (class "Default")
      (node (ref "R76") (pin "1") (pinfunction "1_1") (pintype "passive"))
    )
    (net (code "14") (name "/TH2") (class "Default")
      (node (ref "R81") (pin "1") (pinfunction "1_1") (pintype "passive"))
    )
    (net (code "15") (name "GND") (class "Default")
      (node (ref "C35") (pin "1") (pinfunction "1_1") (pintype "passive"))
      (node (ref "C38") (pin "1") (pinfunction "1_1") (pintype "passive"))
      (node (ref "J27") (pin "1") (pinfunction "1_1") (pintype "passive"))
      (node (ref "J34") (pin "2") (pinfunction "2_2") (pintype "passive"))
      (node (ref "J36") (pin "2") (pinfunction "2_2") (pintype "passive"))
      (node (ref "J53") (pin "2") (pinfunction "2_2") (pintype "passive"))
      (node (ref "J54") (pin "1") (pinfunction "1_1") (pintype "passive"))
      (node (ref "J61") (pin "1") (pinfunction "1_1") (pintype "passive"))
      (node (ref "Q1") (pin "2") (pinfunction "EMITTER_2") (pintype "passive"))
      (node (ref "Q12") (pin "3") (pinfunction "SOURCE_3") (pintype "passive"))
      (node (ref "Q13") (pin "3") (pinfunction "SOURCE_3") (pintype "passive"))
      (node (ref "Q15") (pin "3") (pinfunction "SOURCE_3") (pintype "passive"))
      (node (ref "Q2") (pin "2") (pinfunction "EMITTER_2") (pintype "passive"))
      (node (ref "Q22") (pin "3") (pinfunction "SOURCE_3") (pintype "passive"))
      (node (ref "Q23") (pin "3") (pinfunction "SOURCE_3") (pintype "passive"))
      (node (ref "Q28") (pin "3") (pinfunction "SOURCE_3") (pintype "passive"))
      (node (ref "Q29") (pin "3") (pinfunction "SOURCE_3") (pintype "passive"))
      (node (ref "R134") (pin "2") (pinfunction "2_2") (pintype "passive"))
      (node (ref "R160") (pin "2") (pinfunction "2_2") (pintype "passive"))
      (node (ref "R162") (pin "2") (pinfunction "2_2") (pintype "passive"))
      (node (ref "R66") (pin "2") (pinfunction "2_2") (pintype "passive"))
      (node (ref "R67") (pin "2") (pinfunction "2_2") (pintype "passive"))
      (node (ref "R68") (pin "2") (pinfunction "2_2") (pintype "passive"))
      (node (ref "R77") (pin "2") (pinfunction "2_2") (pintype "passive"))
      (node (ref "R78") (pin "2") (pinfunction "2_2") (pintype "passive"))
      (node (ref "R79") (pin "2") (pinfunction "2_2") (pintype "passive"))
    )
    (net (code "16") (name "Net-(C35-Pad2)") (class "Default")
      (node (ref "C35") (pin "2") (pinfunction "2_2") (pintype "passive"))
      (node (ref "J34") (pin "1") (pinfunction "1_1") (pintype "passive"))
      (node (ref "R73") (pin "1") (pinfunction "1_1") (pintype "passive"))
      (node (ref "R76") (pin "2") (pinfunction "2_2") (pintype "passive"))
    )
    (net (code "17") (name "Net-(C38-Pad2)") (class "Default")
      (node (ref "C38") (pin "2") (pinfunction "2_2") (pintype "passive"))
      (node (ref "J36") (pin "1") (pinfunction "1_1") (pintype "passive"))
      (node (ref "R75") (pin "1") (pinfunction "1_1") (pintype "passive"))
      (node (ref "R81") (pin "2") (pinfunction "2_2") (pintype "passive"))
    )
    (net (code "18") (name "Net-(D18-C)") (class "Default")
      (node (ref "D18") (pin "K") (pinfunction "C_K") (pintype "passive"))
      (node (ref "J28") (pin "2") (pinfunction "2_2") (pintype "passive"))
      (node (ref "Q12") (pin "TAB") (pinfunction "DRAIN_TAB") (pintype "passive"))
    )
    (net (code "19") (name "Net-(D18-PadA)") (class "Default")
      (node (ref "D18") (pin "A") (pinfunction "A_A") (pintype "passive"))
      (node (ref "R170") (pin "1") (pinfunction "1_1") (pintype "passive"))
    )
    (net (code "20") (name "Net-(D19-C)") (class "Default")
      (node (ref "D19") (pin "K") (pinfunction "C_K") (pintype "passive"))
      (node (ref "J29") (pin "2") (pinfunction "2_2") (pintype "passive"))
      (node (ref "Q13") (pin "TAB") (pinfunction "DRAIN_TAB") (pintype "passive"))
    )
    (net (code "21") (name "Net-(D19-PadA)") (class "Default")
      (node (ref "D19") (pin "A") (pinfunction "A_A") (pintype "passive"))
      (node (ref "R185") (pin "1") (pinfunction "1_1") (pintype "passive"))
    )
    (net (code "22") (name "Net-(D20-C)") (class "Default")
      (node (ref "D20") (pin "K") (pinfunction "C_K") (pintype "passive"))
      (node (ref "J31") (pin "2") (pinfunction "2_2") (pintype "passive"))
      (node (ref "Q15") (pin "TAB") (pinfunction "DRAIN_TAB") (pintype "passive"))
    )
    (net (code "23") (name "Net-(D20-PadA)") (class "Default")
      (node (ref "D20") (pin "A") (pinfunction "A_A") (pintype "passive"))
      (node (ref "R193") (pin "1") (pinfunction "1_1") (pintype "passive"))
    )
    (net (code "24") (name "Net-(D21-C)") (class "Default")
      (node (ref "D21") (pin "K") (pinfunction "C_K") (pintype "passive"))
      (node (ref "J32") (pin "2") (pinfunction "2_2") (pintype "passive"))
      (node (ref "Q22") (pin "TAB") (pinfunction "DRAIN_TAB") (pintype "passive"))
    )
    (net (code "25") (name "Net-(D21-PadA)") (class "Default")
      (node (ref "D21") (pin "A") (pinfunction "A_A") (pintype "passive"))
      (node (ref "R194") (pin "1") (pinfunction "1_1") (pintype "passive"))
    )
    (net (code "26") (name "Net-(D22-C)") (class "Default")
      (node (ref "D22") (pin "K") (pinfunction "C_K") (pintype "passive"))
      (node (ref "J54") (pin "2") (pinfunction "2_2") (pintype "passive"))
      (node (ref "Q28") (pin "TAB") (pinfunction "DRAIN_TAB") (pintype "passive"))
    )
    (net (code "27") (name "Net-(D22-PadA)") (class "Default")
      (node (ref "D22") (pin "A") (pinfunction "A_A") (pintype "passive"))
      (node (ref "R195") (pin "1") (pinfunction "1_1") (pintype "passive"))
    )
    (net (code "28") (name "Net-(D23-C)") (class "Default")
      (node (ref "D23") (pin "K") (pinfunction "C_K") (pintype "passive"))
      (node (ref "J52") (pin "2") (pinfunction "2_2") (pintype "passive"))
      (node (ref "Q29") (pin "TAB") (pinfunction "DRAIN_TAB") (pintype "passive"))
    )
    (net (code "29") (name "Net-(D23-PadA)") (class "Default")
      (node (ref "D23") (pin "A") (pinfunction "A_A") (pintype "passive"))
      (node (ref "R196") (pin "1") (pinfunction "1_1") (pintype "passive"))
    )
    (net (code "30") (name "Net-(D24-C)") (class "Default")
      (node (ref "D24") (pin "K") (pinfunction "C_K") (pintype "passive"))
      (node (ref "J33") (pin "2") (pinfunction "2_2") (pintype "passive"))
      (node (ref "Q23") (pin "TAB") (pinfunction "DRAIN_TAB") (pintype "passive"))
    )
    (net (code "31") (name "Net-(D24-PadA)") (class "Default")
      (node (ref "D24") (pin "A") (pinfunction "A_A") (pintype "passive"))
      (node (ref "R197") (pin "1") (pinfunction "1_1") (pintype "passive"))
    )
    (net (code "32") (name "Net-(Q1-BASE)") (class "Default")
      (node (ref "Q1") (pin "1") (pinfunction "BASE_1") (pintype "passive"))
      (node (ref "R62") (pin "2") (pinfunction "2_2") (pintype "passive"))
    )
    (net (code "33") (name "Net-(Q1-COLLECTOR)") (class "Default")
      (node (ref "Q1") (pin "3") (pinfunction "COLLECTOR_3") (pintype "passive"))
      (node (ref "R157") (pin "2") (pinfunction "2_2") (pintype "passive"))
      (node (ref "U19") (pin "2") (pinfunction "CATHODE_2") (pintype "passive"))
    )
    (net (code "34") (name "Net-(Q2-BASE)") (class "Default")
      (node (ref "Q2") (pin "1") (pinfunction "BASE_1") (pintype "passive"))
      (node (ref "R133") (pin "2") (pinfunction "2_2") (pintype "passive"))
    )
    (net (code "35") (name "Net-(Q2-COLLECTOR)") (class "Default")
      (node (ref "Q2") (pin "3") (pinfunction "COLLECTOR_3") (pintype "passive"))
      (node (ref "R158") (pin "2") (pinfunction "2_2") (pintype "passive"))
      (node (ref "U20") (pin "2") (pinfunction "CATHODE_2") (pintype "passive"))
    )
    (net (code "36") (name "Net-(Q12-GATE)") (class "Default")
      (node (ref "Q12") (pin "1") (pinfunction "GATE_1") (pintype "passive"))
      (node (ref "R63") (pin "2") (pinfunction "2_2") (pintype "passive"))
    )
    (net (code "37") (name "Net-(Q13-GATE)") (class "Default")
      (node (ref "Q13") (pin "1") (pinfunction "GATE_1") (pintype "passive"))
      (node (ref "R64") (pin "2") (pinfunction "2_2") (pintype "passive"))
    )
    (net (code "38") (name "Net-(Q15-GATE)") (class "Default")
      (node (ref "Q15") (pin "1") (pinfunction "GATE_1") (pintype "passive"))
      (node (ref "R70") (pin "2") (pinfunction "2_2") (pintype "passive"))
    )
    (net (code "39") (name "Net-(Q22-GATE)") (class "Default")
      (node (ref "Q22") (pin "1") (pinfunction "GATE_1") (pintype "passive"))
      (node (ref "R71") (pin "2") (pinfunction "2_2") (pintype "passive"))
    )
    (net (code "40") (name "Net-(Q23-GATE)") (class "Default")
      (node (ref "Q23") (pin "1") (pinfunction "GATE_1") (pintype "passive"))
      (node (ref "R72") (pin "2") (pinfunction "2_2") (pintype "passive"))
    )
    (net (code "41") (name "Net-(Q28-GATE)") (class "Default")
      (node (ref "Q28") (pin "1") (pinfunction "GATE_1") (pintype "passive"))
      (node (ref "R161") (pin "2") (pinfunction "2_2") (pintype "passive"))
    )
    (net (code "42") (name "Net-(Q29-GATE)") (class "Default")
      (node (ref "Q29") (pin "1") (pinfunction "GATE_1") (pintype "passive"))
      (node (ref "R159") (pin "2") (pinfunction "2_2") (pintype "passive"))
    )
    (net (code "43") (name "Net-(U19-ANODE)") (class "Default")
      (node (ref "R157") (pin "1") (pinfunction "1_1") (pintype "passive"))
      (node (ref "R38") (pin "2") (pinfunction "2_2") (pintype "passive"))
      (node (ref "R65") (pin "2") (pinfunction "2_2") (pintype "passive"))
      (node (ref "U19") (pin "1") (pinfunction "ANODE_1") (pintype "passive"))
    )
    (net (code "44") (name "Net-(U19-COLLECTOR)") (class "Default")
      (node (ref "R35") (pin "1") (pinfunction "1_1") (pintype "passive"))
      (node (ref "U19") (pin "4") (pinfunction "COLLECTOR_4") (pintype "passive"))
    )
    (net (code "45") (name "Net-(U19-EMITTER)") (class "Default")
      (node (ref "J27") (pin "2") (pinfunction "2_2") (pintype "passive"))
      (node (ref "U19") (pin "3") (pinfunction "EMITTER_3") (pintype "passive"))
    )
    (net (code "46") (name "Net-(U20-ANODE)") (class "Default")
      (node (ref "R158") (pin "1") (pinfunction "1_1") (pintype "passive"))
      (node (ref "R39") (pin "2") (pinfunction "2_2") (pintype "passive"))
      (node (ref "R69") (pin "2") (pinfunction "2_2") (pintype "passive"))
      (node (ref "U20") (pin "1") (pinfunction "ANODE_1") (pintype "passive"))
    )
    (net (code "47") (name "Net-(U20-COLLECTOR)") (class "Default")
      (node (ref "R37") (pin "1") (pinfunction "1_1") (pintype "passive"))
      (node (ref "U20") (pin "4") (pinfunction "COLLECTOR_4") (pintype "passive"))
    )
    (net (code "48") (name "Net-(U20-EMITTER)") (class "Default")
      (node (ref "J61") (pin "2") (pinfunction "2_2") (pintype "passive"))
      (node (ref "U20") (pin "3") (pinfunction "EMITTER_3") (pintype "passive"))
    )
  )
)
